# schematic.net
KiCad netlist of a schematic drawn in EasyEDA
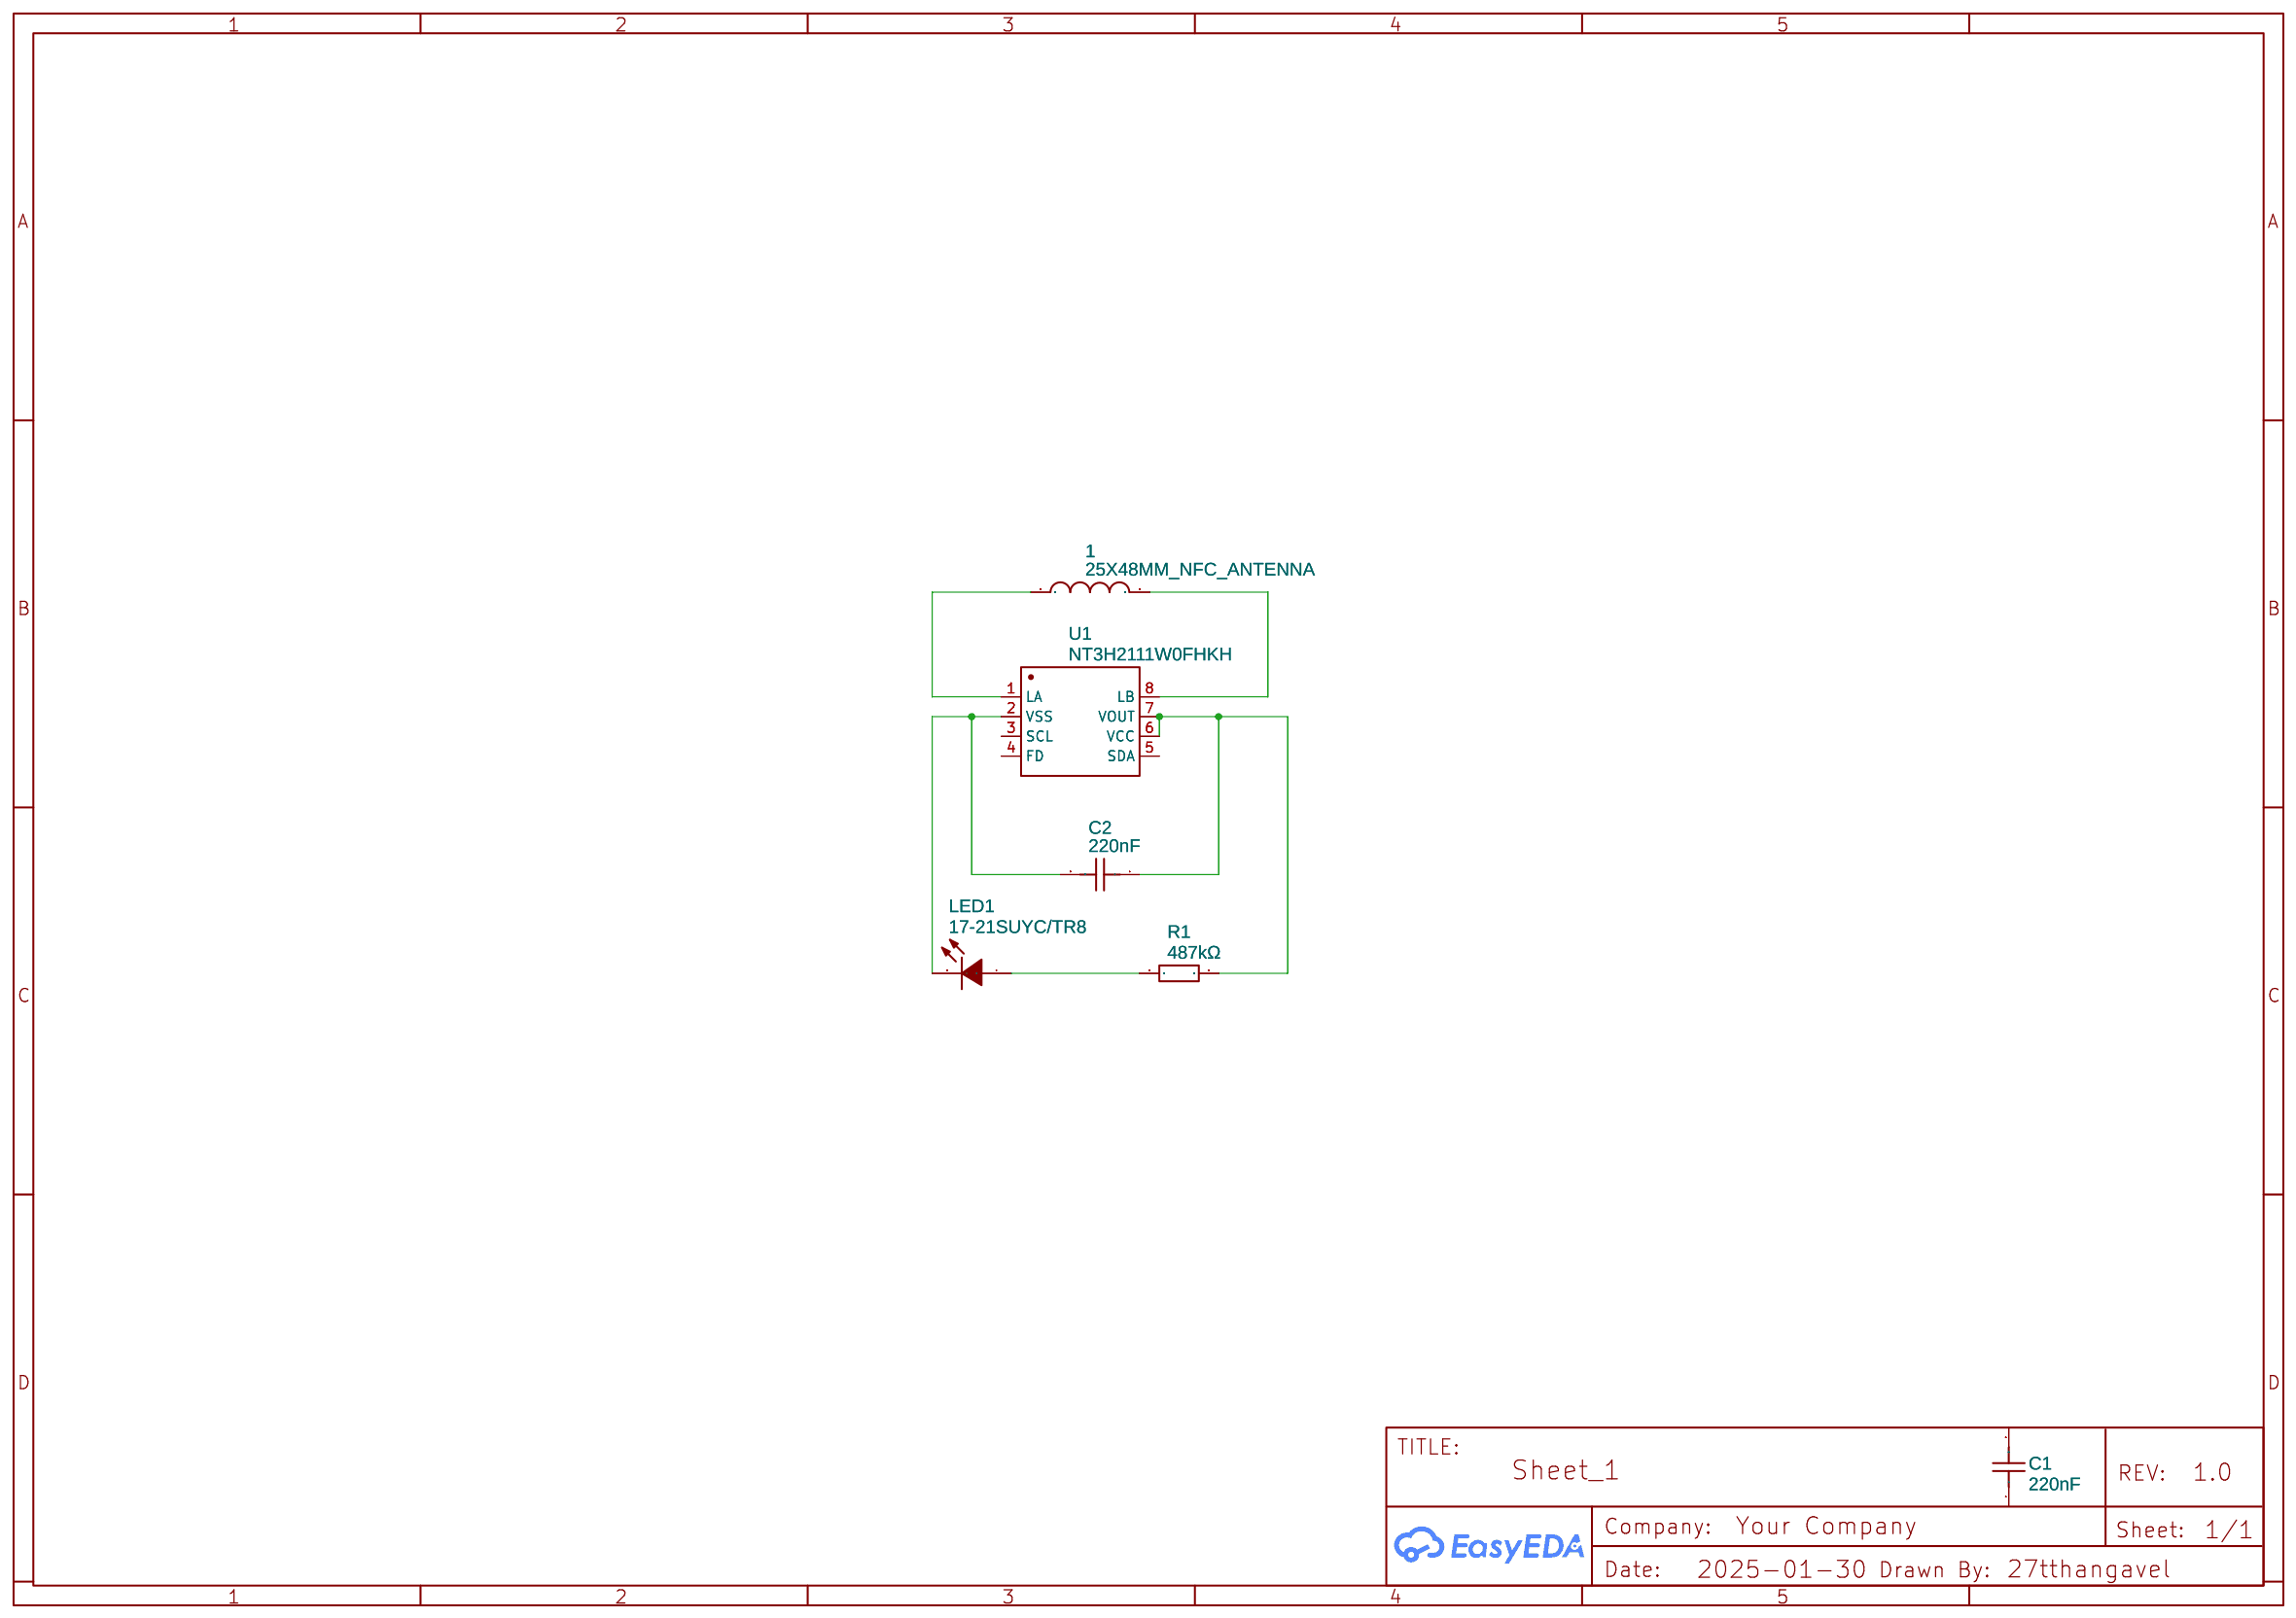
[diagram p0: schematic sheet]

(export (version "E")
  (design (tool "Eeschema 10.0.6"))
  (components
    (comp (ref "1") (value "25X48MM_NFC_ANTENNA") (libsource (lib "") (part "25X48MM_NFC_ANTENNA")))
    (comp (ref "C1")
      (value "220nF")
      (fields
        (field (name "Manufacturer Part") "CL10B224KA8VPNC")
        (field (name "Manufacturer") "SAMSUNG(三星)")
      )
      (libsource (lib "") (part "CL10B224KA8VPNC"))
    )
    (comp (ref "C2")
      (value "220nF")
      (fields
        (field (name "Manufacturer Part") "CL10B224KA8VPNC")
        (field (name "Manufacturer") "SAMSUNG(三星)")
      )
      (libsource (lib "") (part "CL10B224KA8VPNC_1"))
    )
    (comp (ref "LED1")
      (value "17-21SUYC/TR8")
      (fields (field (name "Manufacturer Part") "KT-0805黄灯") (field (name "Manufacturer") "KENTO"))
      (libsource (lib "") (part "17-21SUYC/TR8"))
    )
    (comp (ref "R1")
      (value "487kΩ")
      (fields
        (field (name "Manufacturer Part") "0603WAF4873T5E")
        (field (name "Manufacturer") "UNI-ROYAL(厚声)")
      )
      (libsource (lib "") (part "0603WAF4873T5E"))
    )
    (comp (ref "U1")
      (value "NT3H2111W0FHKH")
      (fields (field (name "Manufacturer") "NXP(恩智浦)"))
      (libsource (lib "") (part "NT3H2111W0FHKH"))
    )
  )
  (nets
    (net (code "1") (name "Net-(LED1-+)") (class "Default")
      (node (ref "LED1") (pin "1") (pinfunction "+_1") (pintype "unspecified"))
      (node (ref "R1") (pin "1") (pinfunction "1_1") (pintype "input"))
    )
    (net (code "2") (name "Net-(LED1--)") (class "Default")
      (node (ref "C2") (pin "2") (pinfunction "2_2") (pintype "unspecified"))
      (node (ref "LED1") (pin "2") (pinfunction "-_2") (pintype "unspecified"))
      (node (ref "U1") (pin "2") (pinfunction "VSS_2") (pintype "unspecified"))
    )
    (net (code "3") (name "Net-(U1-LA)") (class "Default")
      (node (ref "1") (pin "P$1") (pinfunction "P$1_P$1") (pintype "bidirectional"))
      (node (ref "U1") (pin "1") (pinfunction "LA_1") (pintype "unspecified"))
    )
    (net (code "4") (name "Net-(U1-LB)") (class "Default")
      (node (ref "1") (pin "P$2") (pinfunction "P$2_P$2") (pintype "bidirectional"))
      (node (ref "U1") (pin "8") (pinfunction "LB_8") (pintype "unspecified"))
    )
    (net (code "5") (name "Net-(U1-VCC)") (class "Default")
      (node (ref "C2") (pin "1") (pinfunction "1_1") (pintype "unspecified"))
      (node (ref "R1") (pin "2") (pinfunction "2_2") (pintype "input"))
      (node (ref "U1") (pin "6") (pinfunction "VCC_6") (pintype "unspecified"))
      (node (ref "U1") (pin "7") (pinfunction "VOUT_7") (pintype "unspecified"))
    )
    (net (code "6") (name "unconnected-(C1-Pad1)") (class "Default")
      (node (ref "C1") (pin "1") (pinfunction "1_1") (pintype "unspecified"))
    )
    (net (code "7") (name "unconnected-(C1-Pad2)") (class "Default")
      (node (ref "C1") (pin "2") (pinfunction "2_2") (pintype "unspecified"))
    )
    (net (code "8") (name "unconnected-(U1-FD-Pad4)") (class "Default")
      (node (ref "U1") (pin "4") (pinfunction "FD_4") (pintype "unspecified"))
    )
    (net (code "9") (name "unconnected-(U1-SCL-Pad3)") (class "Default")
      (node (ref "U1") (pin "3") (pinfunction "SCL_3") (pintype "unspecified"))
    )
    (net (code "10") (name "unconnected-(U1-SDA-Pad5)") (class "Default")
      (node (ref "U1") (pin "5") (pinfunction "SDA_5") (pintype "unspecified"))
    )
  )
)
